# sensor-bank.net
KiCad netlist of a schematic drawn in Altium Designer
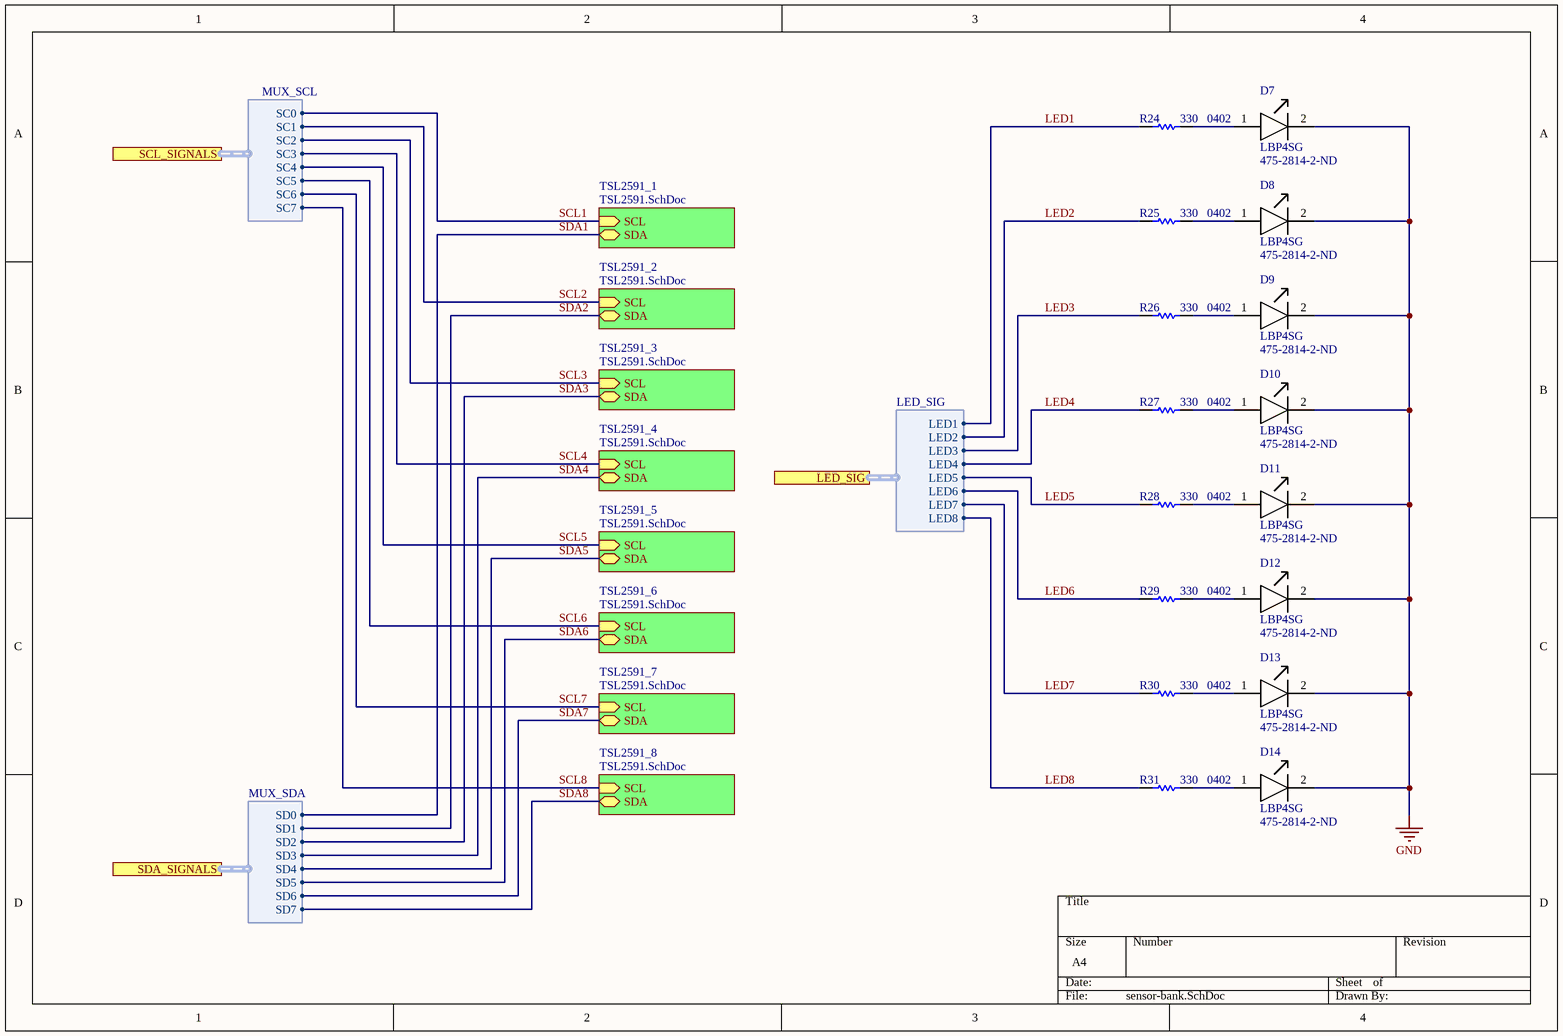
[diagram p0: sensor-bank.SchDoc]

(export (version "E")
  (design (tool "Eeschema 10.0.6"))
  (components
    (comp (ref "D7")
      (value "LBP4SG")
      (footprint "LB P4SG")
      (description "LED BLUE CLEAR SMD BOTTOM ENTRY")
      (fields (field (name "SUPPLIER PART NUMBER 1") "475-2814-2-ND"))
      (libsource (lib "heron-general") (part "LB P4SG"))
    )
    (comp (ref "D8")
      (value "LBP4SG")
      (footprint "LB P4SG")
      (description "LED BLUE CLEAR SMD BOTTOM ENTRY")
      (fields (field (name "SUPPLIER PART NUMBER 1") "475-2814-2-ND"))
      (libsource (lib "heron-general") (part "LB P4SG"))
    )
    (comp (ref "D9")
      (value "LBP4SG")
      (footprint "LB P4SG")
      (description "LED BLUE CLEAR SMD BOTTOM ENTRY")
      (fields (field (name "SUPPLIER PART NUMBER 1") "475-2814-2-ND"))
      (libsource (lib "heron-general") (part "LB P4SG"))
    )
    (comp (ref "D10")
      (value "LBP4SG")
      (footprint "LB P4SG")
      (description "LED BLUE CLEAR SMD BOTTOM ENTRY")
      (fields (field (name "SUPPLIER PART NUMBER 1") "475-2814-2-ND"))
      (libsource (lib "heron-general") (part "LB P4SG"))
    )
    (comp (ref "D11")
      (value "LBP4SG")
      (footprint "LB P4SG")
      (description "LED BLUE CLEAR SMD BOTTOM ENTRY")
      (fields (field (name "SUPPLIER PART NUMBER 1") "475-2814-2-ND"))
      (libsource (lib "heron-general") (part "LB P4SG"))
    )
    (comp (ref "D12")
      (value "LBP4SG")
      (footprint "LB P4SG")
      (description "LED BLUE CLEAR SMD BOTTOM ENTRY")
      (fields (field (name "SUPPLIER PART NUMBER 1") "475-2814-2-ND"))
      (libsource (lib "heron-general") (part "LB P4SG"))
    )
    (comp (ref "D13")
      (value "LBP4SG")
      (footprint "LB P4SG")
      (description "LED BLUE CLEAR SMD BOTTOM ENTRY")
      (fields (field (name "SUPPLIER PART NUMBER 1") "475-2814-2-ND"))
      (libsource (lib "heron-general") (part "LB P4SG"))
    )
    (comp (ref "D14")
      (value "LBP4SG")
      (footprint "LB P4SG")
      (description "LED BLUE CLEAR SMD BOTTOM ENTRY")
      (fields (field (name "SUPPLIER PART NUMBER 1") "475-2814-2-ND"))
      (libsource (lib "heron-general") (part "LB P4SG"))
    )
    (comp (ref "R24")
      (value "0402")
      (footprint "AXIAL-0.3")
      (description "Resistor")
      (fields (field (name "ALTIUM_VALUE") "330") (field (name "PUBLISHER") "Altium Limited"))
      (libsource (lib "Miscellaneous Devices") (part "Res1"))
    )
    (comp (ref "R25")
      (value "0402")
      (footprint "AXIAL-0.3")
      (description "Resistor")
      (fields (field (name "ALTIUM_VALUE") "330") (field (name "PUBLISHER") "Altium Limited"))
      (libsource (lib "Miscellaneous Devices") (part "Res1"))
    )
    (comp (ref "R26")
      (value "0402")
      (footprint "AXIAL-0.3")
      (description "Resistor")
      (fields (field (name "ALTIUM_VALUE") "330") (field (name "PUBLISHER") "Altium Limited"))
      (libsource (lib "Miscellaneous Devices") (part "Res1"))
    )
    (comp (ref "R27")
      (value "0402")
      (footprint "AXIAL-0.3")
      (description "Resistor")
      (fields (field (name "ALTIUM_VALUE") "330") (field (name "PUBLISHER") "Altium Limited"))
      (libsource (lib "Miscellaneous Devices") (part "Res1"))
    )
    (comp (ref "R28")
      (value "0402")
      (footprint "AXIAL-0.3")
      (description "Resistor")
      (fields (field (name "ALTIUM_VALUE") "330") (field (name "PUBLISHER") "Altium Limited"))
      (libsource (lib "Miscellaneous Devices") (part "Res1"))
    )
    (comp (ref "R29")
      (value "0402")
      (footprint "AXIAL-0.3")
      (description "Resistor")
      (fields (field (name "ALTIUM_VALUE") "330") (field (name "PUBLISHER") "Altium Limited"))
      (libsource (lib "Miscellaneous Devices") (part "Res1"))
    )
    (comp (ref "R30")
      (value "0402")
      (footprint "AXIAL-0.3")
      (description "Resistor")
      (fields (field (name "ALTIUM_VALUE") "330") (field (name "PUBLISHER") "Altium Limited"))
      (libsource (lib "Miscellaneous Devices") (part "Res1"))
    )
    (comp (ref "R31")
      (value "0402")
      (footprint "AXIAL-0.3")
      (description "Resistor")
      (fields (field (name "ALTIUM_VALUE") "330") (field (name "PUBLISHER") "Altium Limited"))
      (libsource (lib "Miscellaneous Devices") (part "Res1"))
    )
  )
  (nets
    (net (code "4") (name "/LED1") (class "Default")
      (node (ref "R24") (pin "1") (pinfunction "1_1") (pintype "passive"))
    )
    (net (code "5") (name "/LED2") (class "Default")
      (node (ref "R25") (pin "1") (pinfunction "1_1") (pintype "passive"))
    )
    (net (code "6") (name "/LED3") (class "Default")
      (node (ref "R26") (pin "1") (pinfunction "1_1") (pintype "passive"))
    )
    (net (code "7") (name "/LED4") (class "Default")
      (node (ref "R27") (pin "1") (pinfunction "1_1") (pintype "passive"))
    )
    (net (code "8") (name "/LED5") (class "Default")
      (node (ref "R28") (pin "1") (pinfunction "1_1") (pintype "passive"))
    )
    (net (code "9") (name "/LED6") (class "Default")
      (node (ref "R29") (pin "1") (pinfunction "1_1") (pintype "passive"))
    )
    (net (code "10") (name "/LED7") (class "Default")
      (node (ref "R30") (pin "1") (pinfunction "1_1") (pintype "passive"))
    )
    (net (code "11") (name "/LED8") (class "Default")
      (node (ref "R31") (pin "1") (pinfunction "1_1") (pintype "passive"))
    )
    (net (code "31") (name "GND") (class "Default")
      (node (ref "D10") (pin "2") (pinfunction "Cathode_2") (pintype "passive"))
      (node (ref "D11") (pin "2") (pinfunction "Cathode_2") (pintype "passive"))
      (node (ref "D12") (pin "2") (pinfunction "Cathode_2") (pintype "passive"))
      (node (ref "D13") (pin "2") (pinfunction "Cathode_2") (pintype "passive"))
      (node (ref "D14") (pin "2") (pinfunction "Cathode_2") (pintype "passive"))
      (node (ref "D7") (pin "2") (pinfunction "Cathode_2") (pintype "passive"))
      (node (ref "D8") (pin "2") (pinfunction "Cathode_2") (pintype "passive"))
      (node (ref "D9") (pin "2") (pinfunction "Cathode_2") (pintype "passive"))
    )
    (net (code "32") (name "Net-(D7-Anode)") (class "Default")
      (node (ref "D7") (pin "1") (pinfunction "Anode_1") (pintype "passive"))
      (node (ref "R24") (pin "2") (pinfunction "2_2") (pintype "passive"))
    )
    (net (code "33") (name "Net-(D8-Anode)") (class "Default")
      (node (ref "D8") (pin "1") (pinfunction "Anode_1") (pintype "passive"))
      (node (ref "R25") (pin "2") (pinfunction "2_2") (pintype "passive"))
    )
    (net (code "34") (name "Net-(D9-Anode)") (class "Default")
      (node (ref "D9") (pin "1") (pinfunction "Anode_1") (pintype "passive"))
      (node (ref "R26") (pin "2") (pinfunction "2_2") (pintype "passive"))
    )
    (net (code "35") (name "Net-(D10-Anode)") (class "Default")
      (node (ref "D10") (pin "1") (pinfunction "Anode_1") (pintype "passive"))
      (node (ref "R27") (pin "2") (pinfunction "2_2") (pintype "passive"))
    )
    (net (code "36") (name "Net-(D11-Anode)") (class "Default")
      (node (ref "D11") (pin "1") (pinfunction "Anode_1") (pintype "passive"))
      (node (ref "R28") (pin "2") (pinfunction "2_2") (pintype "passive"))
    )
    (net (code "37") (name "Net-(D12-Anode)") (class "Default")
      (node (ref "D12") (pin "1") (pinfunction "Anode_1") (pintype "passive"))
      (node (ref "R29") (pin "2") (pinfunction "2_2") (pintype "passive"))
    )
    (net (code "38") (name "Net-(D13-Anode)") (class "Default")
      (node (ref "D13") (pin "1") (pinfunction "Anode_1") (pintype "passive"))
      (node (ref "R30") (pin "2") (pinfunction "2_2") (pintype "passive"))
    )
    (net (code "39") (name "Net-(D14-Anode)") (class "Default")
      (node (ref "D14") (pin "1") (pinfunction "Anode_1") (pintype "passive"))
      (node (ref "R31") (pin "2") (pinfunction "2_2") (pintype "passive"))
    )
  )
)
